# M7-Buck_5V.net
KiCad netlist of a schematic drawn in Altium Designer
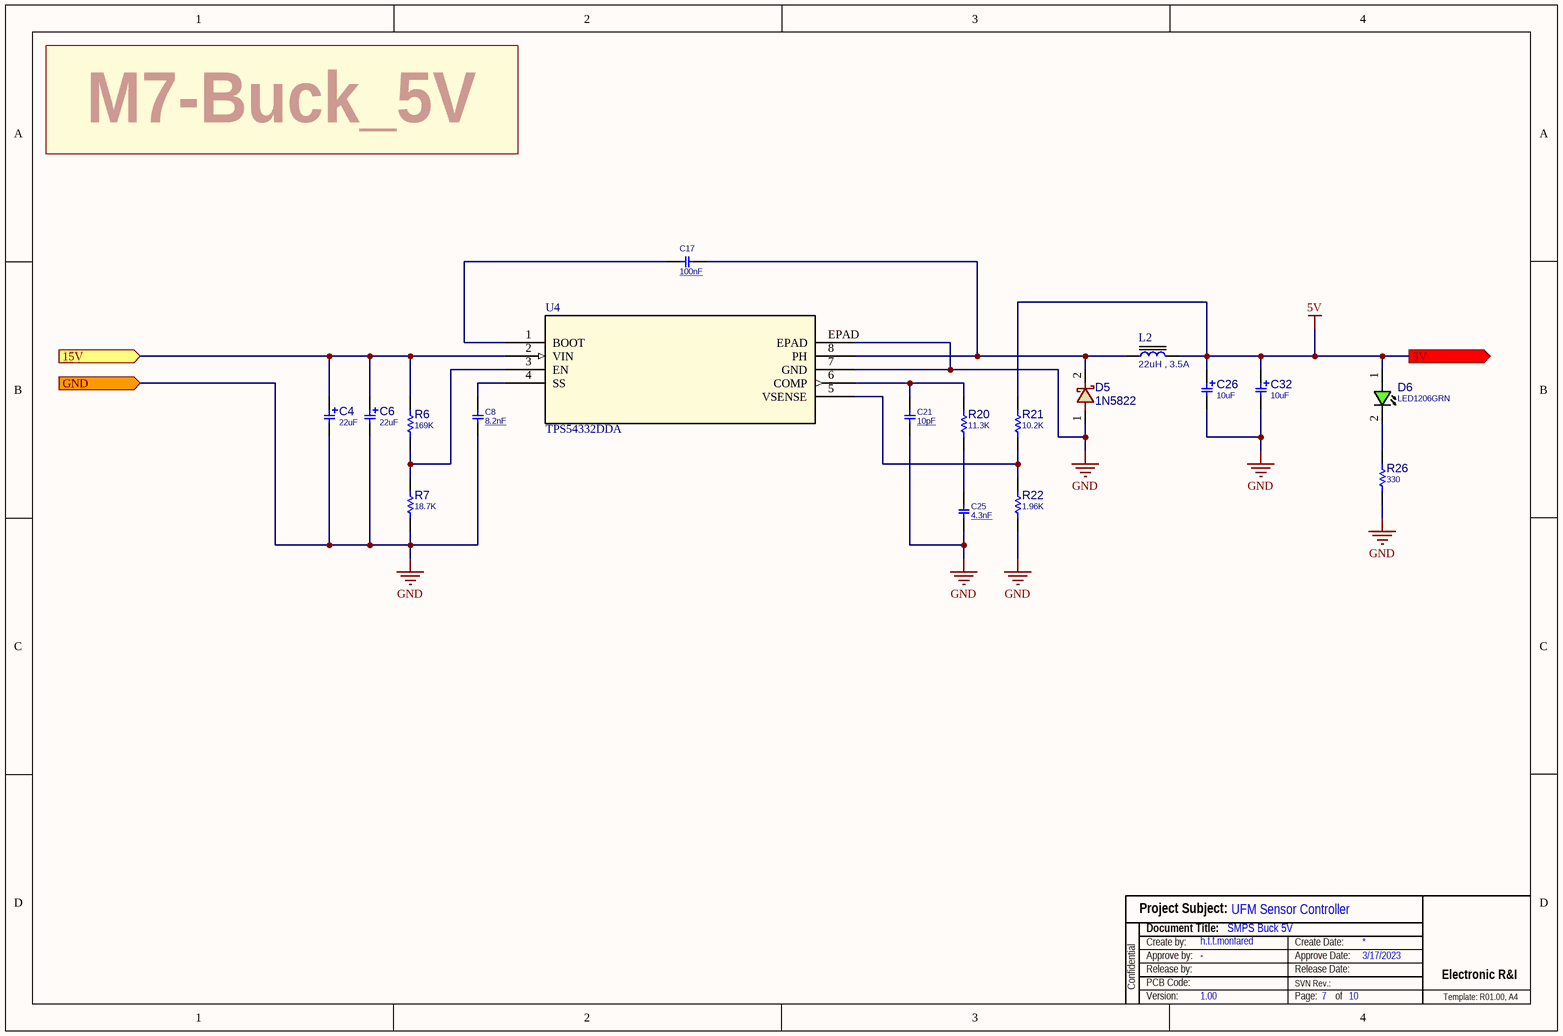
[diagram p0: M7-Buck_5V.SchDoc]

(export (version "E")
  (design (tool "Eeschema 10.0.6"))
  (components
    (comp (ref "C4")
      (value "22uF")
      (footprint "C1206")
      (description "CAP, THD, ELEC,")
      (fields (field (name "MANF_P#") "MANF_PART#") (field (name "MANF") "MANF"))
      (libsource (lib "passive") (part "CAP_SMD_EL"))
    )
    (comp (ref "C6")
      (value "22uF")
      (footprint "C1206")
      (description "CAP, THD, ELEC,")
      (fields (field (name "MANF_P#") "MANF_PART#") (field (name "MANF") "MANF"))
      (libsource (lib "passive") (part "CAP_SMD_EL"))
    )
    (comp (ref "C8")
      (value "8.2nF")
      (footprint "C1206")
      (description "CAP, MLCC, 1nF, 50V, C0G, 10%, 0402")
      (fields (field (name "MANF_P#") "MANF_PART#") (field (name "MANF") "Murata"))
      (libsource (lib "passive") (part "CAP_SMD_MLCC"))
    )
    (comp (ref "C17")
      (value "100nF")
      (footprint "C1206")
      (description "CAP, MLCC, 1nF, 50V, C0G, 10%, 0402")
      (fields (field (name "MANF_P#") "MANF_PART#") (field (name "MANF") "Murata"))
      (libsource (lib "passive") (part "CAP_SMD_MLCC"))
    )
    (comp (ref "C21")
      (value "10pF")
      (footprint "C1206")
      (description "CAP, MLCC, 1nF, 50V, C0G, 10%, 0402")
      (fields (field (name "MANF_P#") "MANF_PART#") (field (name "MANF") "Murata"))
      (libsource (lib "passive") (part "CAP_SMD_MLCC"))
    )
    (comp (ref "C25")
      (value "4.3nF")
      (footprint "C1206")
      (description "CAP, MLCC, 1nF, 50V, C0G, 10%, 0402")
      (fields (field (name "MANF_P#") "MANF_PART#") (field (name "MANF") "Murata"))
      (libsource (lib "passive") (part "CAP_SMD_MLCC"))
    )
    (comp (ref "C26")
      (value "10uF")
      (footprint "C1206")
      (description "CAP, THD, ELEC,")
      (fields (field (name "MANF_P#") "MANF_PART#") (field (name "MANF") "MANF"))
      (libsource (lib "passive") (part "CAP_SMD_EL"))
    )
    (comp (ref "C32")
      (value "10uF")
      (footprint "C1206")
      (description "CAP, THD, ELEC,")
      (fields (field (name "MANF_P#") "MANF_PART#") (field (name "MANF") "MANF"))
      (libsource (lib "passive") (part "CAP_SMD_EL"))
    )
    (comp (ref "D5")
      (value "1N5822")
      (footprint "D_AX06_DO27")
      (description "DIODE, SCHOTTKY, 40V, 3A")
      (fields (field (name "MANF") "Diodes"))
      (libsource (lib "diode") (part "DIODE_THD_SCHOTTKY_1N5822"))
    )
    (comp (ref "D6")
      (value "LED1206GRN")
      (footprint "LED1206GRN")
      (description "LED, SMD, 1206, GREEN")
      (libsource (lib "led(diode)") (part "LED_SMD_1206_GRN"))
    )
    (comp (ref "L2")
      (value "22uH , 3.5A")
      (footprint "L_12")
      (description "INDUCTOR, THD")
      (libsource (lib "passive") (part "IND_THD"))
    )
    (comp (ref "R6")
      (value "169K")
      (footprint "R1206")
      (description "RESISTOR, SMD")
      (fields (field (name "MANF_P#") "RK73H1ETTP4701F") (field (name "MANF") "KOA SPEER"))
      (libsource (lib "passive") (part "RES_SMD"))
    )
    (comp (ref "R7")
      (value "18.7K")
      (footprint "R1206")
      (description "RESISTOR, SMD")
      (fields (field (name "MANF_P#") "RK73H1ETTP4701F") (field (name "MANF") "KOA SPEER"))
      (libsource (lib "passive") (part "RES_SMD"))
    )
    (comp (ref "R20")
      (value "11.3K")
      (footprint "R1206")
      (description "RESISTOR, SMD")
      (fields (field (name "MANF_P#") "RK73H1ETTP4701F") (field (name "MANF") "KOA SPEER"))
      (libsource (lib "passive") (part "RES_SMD"))
    )
    (comp (ref "R21")
      (value "10.2K")
      (footprint "R1206")
      (description "RESISTOR, SMD")
      (fields (field (name "MANF_P#") "RK73H1ETTP4701F") (field (name "MANF") "KOA SPEER"))
      (libsource (lib "passive") (part "RES_SMD"))
    )
    (comp (ref "R22")
      (value "1.96K")
      (footprint "R1206")
      (description "RESISTOR, SMD")
      (fields (field (name "MANF_P#") "RK73H1ETTP4701F") (field (name "MANF") "KOA SPEER"))
      (libsource (lib "passive") (part "RES_SMD"))
    )
    (comp (ref "R26")
      (value "330")
      (footprint "R1206")
      (description "RESISTOR, SMD")
      (fields (field (name "MANF_P#") "RK73H1ETTP4701F") (field (name "MANF") "KOA SPEER"))
      (libsource (lib "passive") (part "RES_SMD"))
    )
    (comp (ref "U4")
      (value "TPS54332DDA")
      (footprint "SO_8T")
      (description "No Description Available")
      (fields (field (name "COPYRIGHT") "Copyright (C) 2022 Ultra Librarian. All rights reserved."))
      (libsource (lib "TPS54332DDA") (part "TPS54332DDA"))
    )
  )
  (nets
    (net (code "1") (name "/15V") (class "Default")
      (node (ref "C4") (pin "1") (pinfunction "1_1") (pintype "passive"))
      (node (ref "C6") (pin "1") (pinfunction "1_1") (pintype "passive"))
      (node (ref "R6") (pin "2") (pinfunction "2_2") (pintype "passive"))
      (node (ref "U4") (pin "2") (pinfunction "VIN_2") (pintype "input"))
    )
    (net (code "2") (name "5V") (class "Default")
      (node (ref "C26") (pin "1") (pinfunction "1_1") (pintype "passive"))
      (node (ref "C32") (pin "1") (pinfunction "1_1") (pintype "passive"))
      (node (ref "D6") (pin "1") (pinfunction "ANODE_1") (pintype "passive"))
      (node (ref "L2") (pin "2") (pinfunction "2_2") (pintype "passive"))
      (node (ref "R21") (pin "2") (pinfunction "2_2") (pintype "passive"))
    )
    (net (code "3") (name "GND") (class "Default")
      (node (ref "C21") (pin "1") (pinfunction "1_1") (pintype "passive"))
      (node (ref "C25") (pin "1") (pinfunction "1_1") (pintype "passive"))
      (node (ref "C26") (pin "2") (pinfunction "2_2") (pintype "passive"))
      (node (ref "C32") (pin "2") (pinfunction "2_2") (pintype "passive"))
      (node (ref "C4") (pin "2") (pinfunction "2_2") (pintype "passive"))
      (node (ref "C6") (pin "2") (pinfunction "2_2") (pintype "passive"))
      (node (ref "C8") (pin "1") (pinfunction "1_1") (pintype "passive"))
      (node (ref "D5") (pin "1") (pinfunction "A_1") (pintype "passive"))
      (node (ref "R22") (pin "1") (pinfunction "1_1") (pintype "passive"))
      (node (ref "R26") (pin "1") (pinfunction "1_1") (pintype "passive"))
      (node (ref "R7") (pin "1") (pinfunction "1_1") (pintype "passive"))
      (node (ref "U4") (pin "7") (pinfunction "GND_7") (pintype "power_in"))
      (node (ref "U4") (pin "EPAD") (pinfunction "EPAD_EPAD") (pintype "passive"))
    )
    (net (code "4") (name "Net-(C25-Pad2)") (class "Default")
      (node (ref "C25") (pin "2") (pinfunction "2_2") (pintype "passive"))
      (node (ref "R20") (pin "1") (pinfunction "1_1") (pintype "passive"))
    )
    (net (code "5") (name "Net-(D5-K)") (class "Default")
      (node (ref "C17") (pin "2") (pinfunction "2_2") (pintype "passive"))
      (node (ref "D5") (pin "2") (pinfunction "K_2") (pintype "passive"))
      (node (ref "L2") (pin "1") (pinfunction "1_1") (pintype "passive"))
      (node (ref "U4") (pin "8") (pinfunction "PH_8") (pintype "power_in"))
    )
    (net (code "6") (name "Net-(D6-CATHODE)") (class "Default")
      (node (ref "D6") (pin "2") (pinfunction "CATHODE_2") (pintype "passive"))
      (node (ref "R26") (pin "2") (pinfunction "2_2") (pintype "passive"))
    )
    (net (code "7") (name "Net-(U4-BOOT)") (class "Default")
      (node (ref "C17") (pin "1") (pinfunction "1_1") (pintype "passive"))
      (node (ref "U4") (pin "1") (pinfunction "BOOT_1") (pintype "passive"))
    )
    (net (code "8") (name "Net-(U4-COMP)") (class "Default")
      (node (ref "C21") (pin "2") (pinfunction "2_2") (pintype "passive"))
      (node (ref "R20") (pin "2") (pinfunction "2_2") (pintype "passive"))
      (node (ref "U4") (pin "6") (pinfunction "COMP_6") (pintype "output"))
    )
    (net (code "9") (name "Net-(U4-EN)") (class "Default")
      (node (ref "R6") (pin "1") (pinfunction "1_1") (pintype "passive"))
      (node (ref "R7") (pin "2") (pinfunction "2_2") (pintype "passive"))
      (node (ref "U4") (pin "3") (pinfunction "EN_3") (pintype "passive"))
    )
    (net (code "10") (name "Net-(U4-SS)") (class "Default")
      (node (ref "C8") (pin "2") (pinfunction "2_2") (pintype "passive"))
      (node (ref "U4") (pin "4") (pinfunction "SS_4") (pintype "passive"))
    )
    (net (code "11") (name "Net-(U4-VSENSE)") (class "Default")
      (node (ref "R21") (pin "1") (pinfunction "1_1") (pintype "passive"))
      (node (ref "R22") (pin "2") (pinfunction "2_2") (pintype "passive"))
      (node (ref "U4") (pin "5") (pinfunction "VSENSE_5") (pintype "passive"))
    )
  )
)
